# btle_board_R0_1.net
KiCad netlist of a schematic drawn in EAGLE
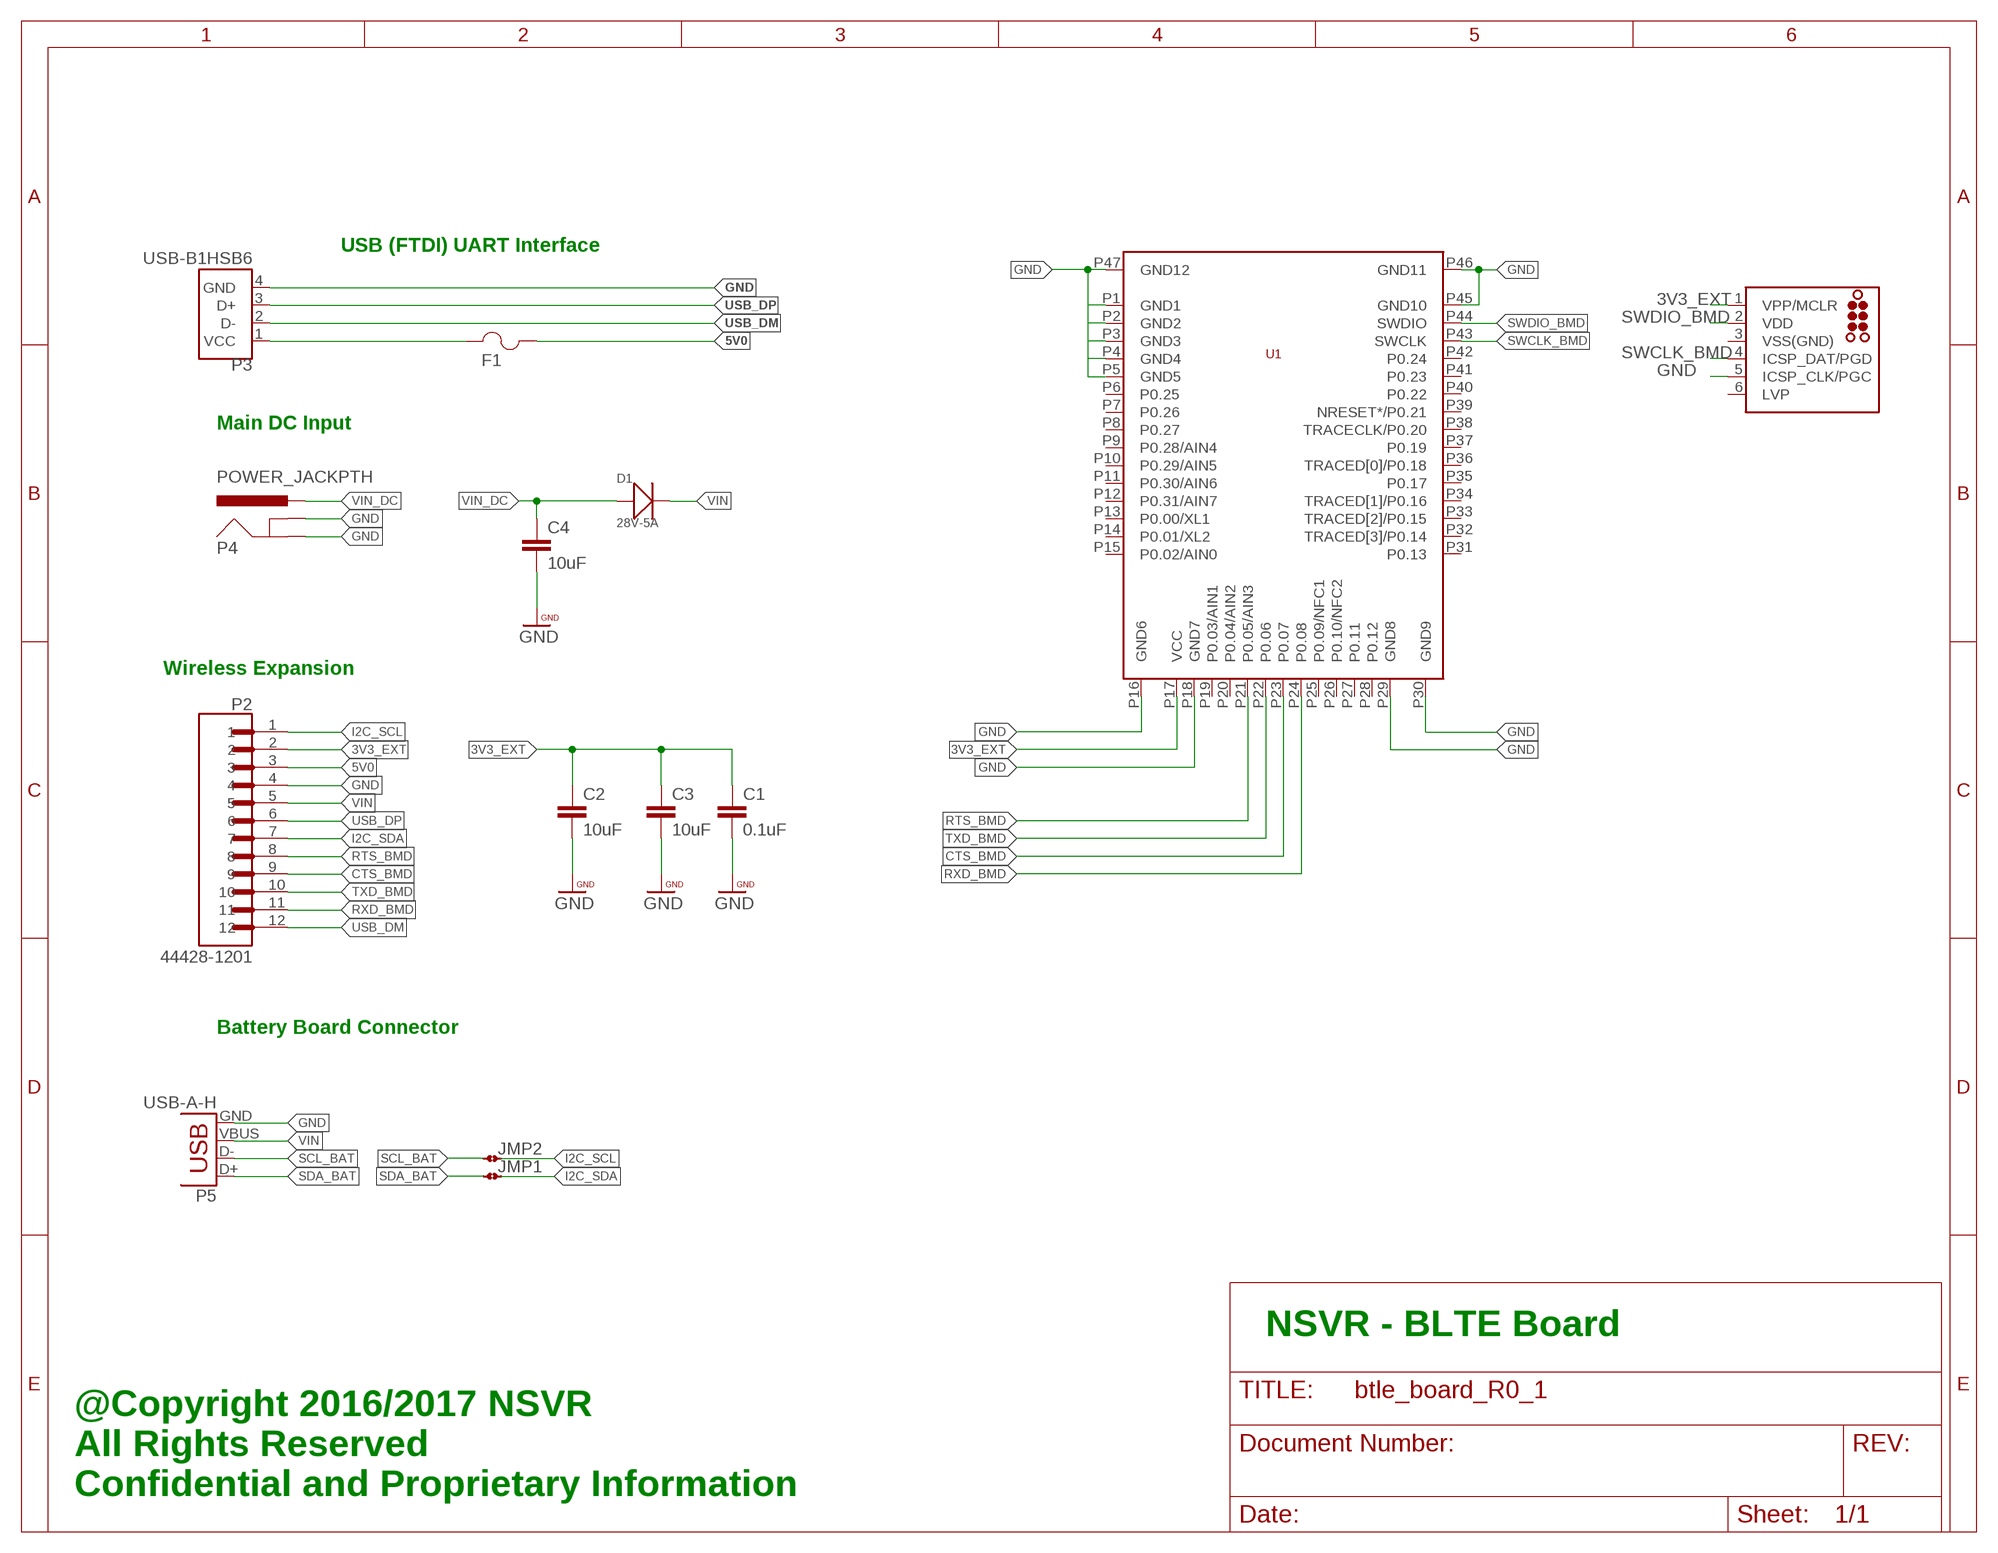
[diagram p0: schematic, sheet 1]

(export (version "E")
  (design (tool "Eeschema 10.0.6"))
  (components
    (comp (ref "C1")
      (value "0.1uF")
      (footprint "eagle-import:0603-CAP")
      (libsource (lib "eagle-import") (part "CAP0603-CAP"))
    )
    (comp (ref "C2")
      (value "10uF")
      (footprint "eagle-import:0603-CAP")
      (libsource (lib "eagle-import") (part "CAP0603-CAP"))
    )
    (comp (ref "C3")
      (value "10uF")
      (footprint "eagle-import:0603-CAP")
      (libsource (lib "eagle-import") (part "CAP0603-CAP"))
    )
    (comp (ref "C4")
      (value "10uF")
      (footprint "eagle-import:0603-CAP")
      (libsource (lib "eagle-import") (part "CAP0603-CAP"))
    )
    (comp (ref "D1")
      (value "28V-5A")
      (footprint "eagle-import:DO-214AA")
      (fields (field (name "MPN") "SS54B"))
      (libsource (lib "eagle-import") (part "SMD-DIODE-SCHOTTKY-28V-5A(DO-214AA)"))
    )
    (comp (ref "F1")
      (value "1206L050YR")
      (footprint "eagle-import:1206LSERIES")
      (fields (field (name "COPYRIGHT") "Copyright C 2015 Accelerated Designs. All rights reserved"))
      (libsource (lib "eagle-import") (part "1206L050YR"))
    )
    (comp (ref "JMP1")
      (value "JMP-2-NO-0402")
      (footprint "eagle-import:JMP-2-NO-0402")
      (libsource (lib "eagle-import") (part "JMP-2-NO-0402"))
    )
    (comp (ref "JMP2")
      (value "JMP-2-NO-0402")
      (footprint "eagle-import:JMP-2-NO-0402")
      (libsource (lib "eagle-import") (part "JMP-2-NO-0402"))
    )
    (comp (ref "P1")
      (value "TC2030-MCP-NL")
      (footprint "eagle-import:TC2030-MCP-NL")
      (libsource (lib "eagle-import") (part "TC2030-MCP-NL"))
    )
    (comp (ref "P2")
      (value "44428-1201")
      (footprint "eagle-import:MOLEX_44428-1201")
      (fields (field (name "MF") "Molex"))
      (libsource (lib "eagle-import") (part "44428-1201"))
    )
    (comp (ref "P3")
      (value "USB-B1HSB6")
      (footprint "eagle-import:OST_USB-B1HSB6")
      (fields (field (name "MF") "On Shore Technology"))
      (libsource (lib "eagle-import") (part "USB-B1HSB6"))
    )
    (comp (ref "P4")
      (value "POWER_JACKPTH")
      (footprint "eagle-import:POWER_JACK_PTH")
      (libsource (lib "eagle-import") (part "POWER_JACKPTH"))
    )
    (comp (ref "P5")
      (value "USB-A-H")
      (footprint "eagle-import:USB-A-H")
      (libsource (lib "eagle-import") (part "USB-A-H"))
    )
    (comp (ref "U1")
      (value "BMD-300")
      (footprint "eagle-import:BMD-300")
      (libsource (lib "eagle-import") (part "BMD-300"))
    )
  )
  (nets
    (net (code "1") (name "/VSS(GND)") (class "Default")
      (node (ref "P1") (pin "3") (pinfunction "VSS(GND)_3") (pintype "power_in"))
    )
    (net (code "2") (name "3V3_EXT") (class "Default")
      (node (ref "C1") (pin "1") (pinfunction "1_1") (pintype "passive"))
      (node (ref "C2") (pin "1") (pinfunction "1_1") (pintype "passive"))
      (node (ref "C3") (pin "1") (pinfunction "1_1") (pintype "passive"))
      (node (ref "P1") (pin "1") (pinfunction "VPP/MCLR_1") (pintype "passive"))
      (node (ref "P2") (pin "2") (pinfunction "2_2") (pintype "passive"))
      (node (ref "U1") (pin "P17") (pinfunction "VCC_P17") (pintype "bidirectional"))
    )
    (net (code "3") (name "5V0") (class "Default")
      (node (ref "F1") (pin "2") (pinfunction "2_2") (pintype "passive"))
      (node (ref "P2") (pin "3") (pinfunction "3_3") (pintype "passive"))
    )
    (net (code "4") (name "CTS_BMD") (class "Default")
      (node (ref "P2") (pin "9") (pinfunction "9_9") (pintype "passive"))
      (node (ref "U1") (pin "P23") (pinfunction "P0.07_P23") (pintype "bidirectional"))
    )
    (net (code "5") (name "GND") (class "Default")
      (node (ref "C1") (pin "2") (pinfunction "2_2") (pintype "passive"))
      (node (ref "C2") (pin "2") (pinfunction "2_2") (pintype "passive"))
      (node (ref "C3") (pin "2") (pinfunction "2_2") (pintype "passive"))
      (node (ref "C4") (pin "2") (pinfunction "2_2") (pintype "passive"))
      (node (ref "P1") (pin "5") (pinfunction "ICSP_CLK/PGC_5") (pintype "output"))
      (node (ref "P2") (pin "4") (pinfunction "4_4") (pintype "passive"))
      (node (ref "P3") (pin "4") (pinfunction "GND_4") (pintype "power_in"))
      (node (ref "P4") (pin "GND") (pinfunction "GND_GND") (pintype "bidirectional"))
      (node (ref "P4") (pin "GNDBREAK") (pinfunction "GNDBREAK_GNDBREAK") (pintype "bidirectional"))
      (node (ref "P5") (pin "GND") (pinfunction "GND_GND") (pintype "bidirectional"))
      (node (ref "U1") (pin "P1") (pinfunction "GND1_P1") (pintype "bidirectional"))
      (node (ref "U1") (pin "P16") (pinfunction "GND6_P16") (pintype "bidirectional"))
      (node (ref "U1") (pin "P18") (pinfunction "GND7_P18") (pintype "bidirectional"))
      (node (ref "U1") (pin "P2") (pinfunction "GND2_P2") (pintype "bidirectional"))
      (node (ref "U1") (pin "P29") (pinfunction "GND8_P29") (pintype "bidirectional"))
      (node (ref "U1") (pin "P3") (pinfunction "GND3_P3") (pintype "bidirectional"))
      (node (ref "U1") (pin "P30") (pinfunction "GND9_P30") (pintype "bidirectional"))
      (node (ref "U1") (pin "P4") (pinfunction "GND4_P4") (pintype "bidirectional"))
      (node (ref "U1") (pin "P45") (pinfunction "GND10_P45") (pintype "bidirectional"))
      (node (ref "U1") (pin "P46") (pinfunction "GND11_P46") (pintype "bidirectional"))
      (node (ref "U1") (pin "P47") (pinfunction "GND12_P47") (pintype "bidirectional"))
      (node (ref "U1") (pin "P5") (pinfunction "GND5_P5") (pintype "bidirectional"))
    )
    (net (code "6") (name "I2C_SCL") (class "Default")
      (node (ref "JMP2") (pin "2") (pinfunction "2_2") (pintype "passive"))
      (node (ref "P2") (pin "1") (pinfunction "1_1") (pintype "passive"))
    )
    (net (code "7") (name "I2C_SDA") (class "Default")
      (node (ref "JMP1") (pin "2") (pinfunction "2_2") (pintype "passive"))
      (node (ref "P2") (pin "7") (pinfunction "7_7") (pintype "passive"))
    )
    (net (code "8") (name "Net-(P3-VCC)") (class "Default")
      (node (ref "F1") (pin "1") (pinfunction "1_1") (pintype "passive"))
      (node (ref "P3") (pin "1") (pinfunction "VCC_1") (pintype "power_in"))
    )
    (net (code "9") (name "RTS_BMD") (class "Default")
      (node (ref "P2") (pin "8") (pinfunction "8_8") (pintype "passive"))
      (node (ref "U1") (pin "P21") (pinfunction "P0.05/AIN3_P21") (pintype "bidirectional"))
    )
    (net (code "10") (name "RXD_BMD") (class "Default")
      (node (ref "P2") (pin "11") (pinfunction "11_11") (pintype "passive"))
      (node (ref "U1") (pin "P24") (pinfunction "P0.08_P24") (pintype "bidirectional"))
    )
    (net (code "11") (name "SCL_BAT") (class "Default")
      (node (ref "JMP2") (pin "1") (pinfunction "1_1") (pintype "passive"))
      (node (ref "P5") (pin "D-") (pinfunction "D-_D-") (pintype "bidirectional"))
    )
    (net (code "12") (name "SDA_BAT") (class "Default")
      (node (ref "JMP1") (pin "1") (pinfunction "1_1") (pintype "passive"))
      (node (ref "P5") (pin "D+") (pinfunction "D+_D+") (pintype "bidirectional"))
    )
    (net (code "13") (name "SWCLK_BMD") (class "Default")
      (node (ref "P1") (pin "4") (pinfunction "ICSP_DAT/PGD_4") (pintype "bidirectional"))
      (node (ref "U1") (pin "P43") (pinfunction "SWCLK_P43") (pintype "bidirectional"))
    )
    (net (code "14") (name "SWDIO_BMD") (class "Default")
      (node (ref "P1") (pin "2") (pinfunction "VDD_2") (pintype "power_in"))
      (node (ref "U1") (pin "P44") (pinfunction "SWDIO_P44") (pintype "bidirectional"))
    )
    (net (code "15") (name "TXD_BMD") (class "Default")
      (node (ref "P2") (pin "10") (pinfunction "10_10") (pintype "passive"))
      (node (ref "U1") (pin "P22") (pinfunction "P0.06_P22") (pintype "bidirectional"))
    )
    (net (code "16") (name "USB_DM") (class "Default")
      (node (ref "P2") (pin "12") (pinfunction "12_12") (pintype "passive"))
      (node (ref "P3") (pin "2") (pinfunction "D-_2") (pintype "bidirectional"))
    )
    (net (code "17") (name "USB_DP") (class "Default")
      (node (ref "P2") (pin "6") (pinfunction "6_6") (pintype "passive"))
      (node (ref "P3") (pin "3") (pinfunction "D+_3") (pintype "bidirectional"))
    )
    (net (code "18") (name "VIN") (class "Default")
      (node (ref "D1") (pin "-") (pinfunction "-_-") (pintype "passive"))
      (node (ref "P2") (pin "5") (pinfunction "5_5") (pintype "passive"))
      (node (ref "P5") (pin "VBUS") (pinfunction "VBUS_VBUS") (pintype "bidirectional"))
    )
    (net (code "19") (name "VIN_DC") (class "Default")
      (node (ref "C4") (pin "1") (pinfunction "1_1") (pintype "passive"))
      (node (ref "D1") (pin "+") (pinfunction "+_+") (pintype "passive"))
      (node (ref "P4") (pin "PWR") (pinfunction "PWR_PWR") (pintype "bidirectional"))
    )
    (net (code "20") (name "unconnected-(P1-LVP-Pad6)") (class "Default")
      (node (ref "P1") (pin "6") (pinfunction "LVP_6") (pintype "bidirectional"))
    )
    (net (code "21") (name "unconnected-(U1-NRESET*{slash}P0.21-PadP39)") (class "Default")
      (node (ref "U1") (pin "P39") (pinfunction "NRESET*/P0.21_P39") (pintype "bidirectional"))
    )
    (net (code "22") (name "unconnected-(U1-P0.00{slash}XL1-PadP13)") (class "Default")
      (node (ref "U1") (pin "P13") (pinfunction "P0.00/XL1_P13") (pintype "bidirectional"))
    )
    (net (code "23") (name "unconnected-(U1-P0.01{slash}XL2-PadP14)") (class "Default")
      (node (ref "U1") (pin "P14") (pinfunction "P0.01/XL2_P14") (pintype "bidirectional"))
    )
    (net (code "24") (name "unconnected-(U1-P0.02{slash}AIN0-PadP15)") (class "Default")
      (node (ref "U1") (pin "P15") (pinfunction "P0.02/AIN0_P15") (pintype "bidirectional"))
    )
    (net (code "25") (name "unconnected-(U1-P0.03{slash}AIN1-PadP19)") (class "Default")
      (node (ref "U1") (pin "P19") (pinfunction "P0.03/AIN1_P19") (pintype "bidirectional"))
    )
    (net (code "26") (name "unconnected-(U1-P0.04{slash}AIN2-PadP20)") (class "Default")
      (node (ref "U1") (pin "P20") (pinfunction "P0.04/AIN2_P20") (pintype "bidirectional"))
    )
    (net (code "27") (name "unconnected-(U1-P0.09{slash}NFC1-PadP25)") (class "Default")
      (node (ref "U1") (pin "P25") (pinfunction "P0.09/NFC1_P25") (pintype "bidirectional"))
    )
    (net (code "28") (name "unconnected-(U1-P0.10{slash}NFC2-PadP26)") (class "Default")
      (node (ref "U1") (pin "P26") (pinfunction "P0.10/NFC2_P26") (pintype "bidirectional"))
    )
    (net (code "29") (name "unconnected-(U1-P0.11-PadP27)") (class "Default")
      (node (ref "U1") (pin "P27") (pinfunction "P0.11_P27") (pintype "bidirectional"))
    )
    (net (code "30") (name "unconnected-(U1-P0.12-PadP28)") (class "Default")
      (node (ref "U1") (pin "P28") (pinfunction "P0.12_P28") (pintype "bidirectional"))
    )
    (net (code "31") (name "unconnected-(U1-P0.13-PadP31)") (class "Default")
      (node (ref "U1") (pin "P31") (pinfunction "P0.13_P31") (pintype "bidirectional"))
    )
    (net (code "32") (name "unconnected-(U1-P0.17-PadP35)") (class "Default")
      (node (ref "U1") (pin "P35") (pinfunction "P0.17_P35") (pintype "bidirectional"))
    )
    (net (code "33") (name "unconnected-(U1-P0.19-PadP37)") (class "Default")
      (node (ref "U1") (pin "P37") (pinfunction "P0.19_P37") (pintype "bidirectional"))
    )
    (net (code "34") (name "unconnected-(U1-P0.22-PadP40)") (class "Default")
      (node (ref "U1") (pin "P40") (pinfunction "P0.22_P40") (pintype "bidirectional"))
    )
    (net (code "35") (name "unconnected-(U1-P0.23-PadP41)") (class "Default")
      (node (ref "U1") (pin "P41") (pinfunction "P0.23_P41") (pintype "bidirectional"))
    )
    (net (code "36") (name "unconnected-(U1-P0.24-PadP42)") (class "Default")
      (node (ref "U1") (pin "P42") (pinfunction "P0.24_P42") (pintype "bidirectional"))
    )
    (net (code "37") (name "unconnected-(U1-P0.25-PadP6)") (class "Default")
      (node (ref "U1") (pin "P6") (pinfunction "P0.25_P6") (pintype "bidirectional"))
    )
    (net (code "38") (name "unconnected-(U1-P0.26-PadP7)") (class "Default")
      (node (ref "U1") (pin "P7") (pinfunction "P0.26_P7") (pintype "bidirectional"))
    )
    (net (code "39") (name "unconnected-(U1-P0.27-PadP8)") (class "Default")
      (node (ref "U1") (pin "P8") (pinfunction "P0.27_P8") (pintype "bidirectional"))
    )
    (net (code "40") (name "unconnected-(U1-P0.28{slash}AIN4-PadP9)") (class "Default")
      (node (ref "U1") (pin "P9") (pinfunction "P0.28/AIN4_P9") (pintype "bidirectional"))
    )
    (net (code "41") (name "unconnected-(U1-P0.29{slash}AIN5-PadP10)") (class "Default")
      (node (ref "U1") (pin "P10") (pinfunction "P0.29/AIN5_P10") (pintype "bidirectional"))
    )
    (net (code "42") (name "unconnected-(U1-P0.30{slash}AIN6-PadP11)") (class "Default")
      (node (ref "U1") (pin "P11") (pinfunction "P0.30/AIN6_P11") (pintype "bidirectional"))
    )
    (net (code "43") (name "unconnected-(U1-P0.31{slash}AIN7-PadP12)") (class "Default")
      (node (ref "U1") (pin "P12") (pinfunction "P0.31/AIN7_P12") (pintype "bidirectional"))
    )
    (net (code "44") (name "unconnected-(U1-TRACECLK{slash}P0.20-PadP38)") (class "Default")
      (node (ref "U1") (pin "P38") (pinfunction "TRACECLK/P0.20_P38") (pintype "bidirectional"))
    )
    (net (code "45") (name "unconnected-(U1-TRACED[0]{slash}P0.18-PadP36)") (class "Default")
      (node (ref "U1") (pin "P36") (pinfunction "TRACED[0]/P0.18_P36") (pintype "bidirectional"))
    )
    (net (code "46") (name "unconnected-(U1-TRACED[1]{slash}P0.16-PadP34)") (class "Default")
      (node (ref "U1") (pin "P34") (pinfunction "TRACED[1]/P0.16_P34") (pintype "bidirectional"))
    )
    (net (code "47") (name "unconnected-(U1-TRACED[2]{slash}P0.15-PadP33)") (class "Default")
      (node (ref "U1") (pin "P33") (pinfunction "TRACED[2]/P0.15_P33") (pintype "bidirectional"))
    )
    (net (code "48") (name "unconnected-(U1-TRACED[3]{slash}P0.14-PadP32)") (class "Default")
      (node (ref "U1") (pin "P32") (pinfunction "TRACED[3]/P0.14_P32") (pintype "bidirectional"))
    )
  )
)
